# rudder_shield.net
KiCad netlist of a schematic drawn in EAGLE
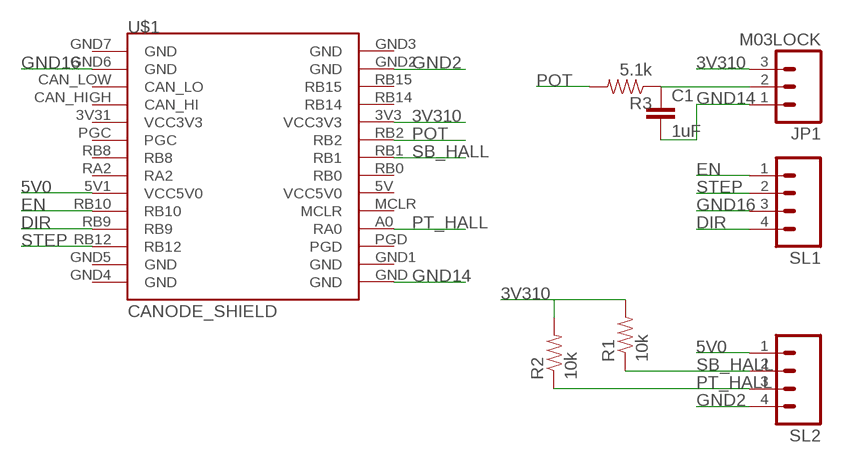
[diagram p0: schematic, sheet 1]

(export (version "E")
  (design (tool "Eeschema 10.0.6"))
  (components
    (comp (ref "C1")
      (value "1uF")
      (footprint "eagle-import:1206")
      (libsource (lib "eagle-import") (part "CAP1206"))
    )
    (comp (ref "JP1")
      (value "M03LOCK")
      (footprint "eagle-import:1X03_LOCK")
      (libsource (lib "eagle-import") (part "M03LOCK"))
    )
    (comp (ref "R1")
      (value "10k")
      (footprint "eagle-import:0805")
      (libsource (lib "eagle-import") (part "RESISTOR0805-RES"))
    )
    (comp (ref "R2")
      (value "10k")
      (footprint "eagle-import:0805")
      (libsource (lib "eagle-import") (part "RESISTOR0805-RES"))
    )
    (comp (ref "R3")
      (value "5.1k")
      (footprint "eagle-import:0805")
      (libsource (lib "eagle-import") (part "RESISTOR0805-RES"))
    )
    (comp (ref "SL1")
      (value "M04LOCK")
      (footprint "eagle-import:1X04_LOCK")
      (libsource (lib "eagle-import") (part "M04LOCK"))
    )
    (comp (ref "SL2")
      (value "M04LOCK")
      (footprint "eagle-import:1X04_LOCK")
      (libsource (lib "eagle-import") (part "M04LOCK"))
    )
    (comp (ref "U$1")
      (value "CANODE_SHIELD")
      (footprint "eagle-import:CANODE_SHIELD")
      (libsource (lib "eagle-import") (part "CANODE_SHIELD"))
    )
  )
  (nets
    (net (code "1") (name "/3V310") (class "Default")
      (node (ref "JP1") (pin "3") (pinfunction "3_3") (pintype "passive"))
      (node (ref "R1") (pin "2") (pinfunction "2_2") (pintype "passive"))
      (node (ref "R2") (pin "2") (pinfunction "2_2") (pintype "passive"))
      (node (ref "U$1") (pin "3V3") (pinfunction "VCC3V3_3V3") (pintype "bidirectional"))
    )
    (net (code "2") (name "/5V0") (class "Default")
      (node (ref "SL2") (pin "1") (pinfunction "1_1") (pintype "passive"))
      (node (ref "U$1") (pin "5V1") (pinfunction "VCC5V0_5V1") (pintype "bidirectional"))
    )
    (net (code "3") (name "/DIR") (class "Default")
      (node (ref "SL1") (pin "4") (pinfunction "4_4") (pintype "passive"))
      (node (ref "U$1") (pin "RB9") (pinfunction "RB9_RB9") (pintype "bidirectional"))
    )
    (net (code "4") (name "/EN") (class "Default")
      (node (ref "SL1") (pin "1") (pinfunction "1_1") (pintype "passive"))
      (node (ref "U$1") (pin "RB10") (pinfunction "RB10_RB10") (pintype "bidirectional"))
    )
    (net (code "5") (name "/GND2") (class "Default")
      (node (ref "SL2") (pin "4") (pinfunction "4_4") (pintype "passive"))
      (node (ref "U$1") (pin "GND2") (pinfunction "GND_GND2") (pintype "bidirectional"))
    )
    (net (code "6") (name "/GND14") (class "Default")
      (node (ref "C1") (pin "2") (pinfunction "2_2") (pintype "passive"))
      (node (ref "JP1") (pin "1") (pinfunction "1_1") (pintype "passive"))
      (node (ref "U$1") (pin "GND") (pinfunction "GND_GND") (pintype "bidirectional"))
    )
    (net (code "7") (name "/GND16") (class "Default")
      (node (ref "SL1") (pin "3") (pinfunction "3_3") (pintype "passive"))
      (node (ref "U$1") (pin "GND6") (pinfunction "GND_GND6") (pintype "bidirectional"))
    )
    (net (code "8") (name "/POT") (class "Default")
      (node (ref "R3") (pin "2") (pinfunction "2_2") (pintype "passive"))
      (node (ref "U$1") (pin "RB2") (pinfunction "RB2_RB2") (pintype "bidirectional"))
    )
    (net (code "9") (name "/PT_HALL") (class "Default")
      (node (ref "R2") (pin "1") (pinfunction "1_1") (pintype "passive"))
      (node (ref "SL2") (pin "3") (pinfunction "3_3") (pintype "passive"))
      (node (ref "U$1") (pin "A0") (pinfunction "RA0_A0") (pintype "bidirectional"))
    )
    (net (code "10") (name "/SB_HALL") (class "Default")
      (node (ref "R1") (pin "1") (pinfunction "1_1") (pintype "passive"))
      (node (ref "SL2") (pin "2") (pinfunction "2_2") (pintype "passive"))
      (node (ref "U$1") (pin "RB1") (pinfunction "RB1_RB1") (pintype "bidirectional"))
    )
    (net (code "11") (name "/STEP") (class "Default")
      (node (ref "SL1") (pin "2") (pinfunction "2_2") (pintype "passive"))
      (node (ref "U$1") (pin "RB12") (pinfunction "RB12_RB12") (pintype "bidirectional"))
    )
    (net (code "12") (name "Net-(C1-Pad1)") (class "Default")
      (node (ref "C1") (pin "1") (pinfunction "1_1") (pintype "passive"))
      (node (ref "JP1") (pin "2") (pinfunction "2_2") (pintype "passive"))
      (node (ref "R3") (pin "1") (pinfunction "1_1") (pintype "passive"))
    )
    (net (code "13") (name "unconnected-(U$1-CAN_HI-PadCAN_HIGH)") (class "Default")
      (node (ref "U$1") (pin "CAN_HIGH") (pinfunction "CAN_HI_CAN_HIGH") (pintype "bidirectional"))
    )
    (net (code "14") (name "unconnected-(U$1-CAN_LO-PadCAN_LOW)") (class "Default")
      (node (ref "U$1") (pin "CAN_LOW") (pinfunction "CAN_LO_CAN_LOW") (pintype "bidirectional"))
    )
    (net (code "15") (name "unconnected-(U$1-GND-PadGND1)") (class "Default")
      (node (ref "U$1") (pin "GND1") (pinfunction "GND_GND1") (pintype "bidirectional"))
    )
    (net (code "16") (name "unconnected-(U$1-GND-PadGND3)") (class "Default")
      (node (ref "U$1") (pin "GND3") (pinfunction "GND_GND3") (pintype "bidirectional"))
    )
    (net (code "17") (name "unconnected-(U$1-GND-PadGND4)") (class "Default")
      (node (ref "U$1") (pin "GND4") (pinfunction "GND_GND4") (pintype "bidirectional"))
    )
    (net (code "18") (name "unconnected-(U$1-GND-PadGND5)") (class "Default")
      (node (ref "U$1") (pin "GND5") (pinfunction "GND_GND5") (pintype "bidirectional"))
    )
    (net (code "19") (name "unconnected-(U$1-GND-PadGND7)") (class "Default")
      (node (ref "U$1") (pin "GND7") (pinfunction "GND_GND7") (pintype "bidirectional"))
    )
    (net (code "20") (name "unconnected-(U$1-PadMCLR)") (class "Default")
      (node (ref "U$1") (pin "MCLR") (pinfunction "MCLR_MCLR") (pintype "bidirectional"))
    )
    (net (code "21") (name "unconnected-(U$1-PadPGC)") (class "Default")
      (node (ref "U$1") (pin "PGC") (pinfunction "PGC_PGC") (pintype "bidirectional"))
    )
    (net (code "22") (name "unconnected-(U$1-PadPGD)") (class "Default")
      (node (ref "U$1") (pin "PGD") (pinfunction "PGD_PGD") (pintype "bidirectional"))
    )
    (net (code "23") (name "unconnected-(U$1-PadRA2)") (class "Default")
      (node (ref "U$1") (pin "RA2") (pinfunction "RA2_RA2") (pintype "bidirectional"))
    )
    (net (code "24") (name "unconnected-(U$1-PadRB0)") (class "Default")
      (node (ref "U$1") (pin "RB0") (pinfunction "RB0_RB0") (pintype "bidirectional"))
    )
    (net (code "25") (name "unconnected-(U$1-PadRB8)") (class "Default")
      (node (ref "U$1") (pin "RB8") (pinfunction "RB8_RB8") (pintype "bidirectional"))
    )
    (net (code "26") (name "unconnected-(U$1-PadRB14)") (class "Default")
      (node (ref "U$1") (pin "RB14") (pinfunction "RB14_RB14") (pintype "bidirectional"))
    )
    (net (code "27") (name "unconnected-(U$1-PadRB15)") (class "Default")
      (node (ref "U$1") (pin "RB15") (pinfunction "RB15_RB15") (pintype "bidirectional"))
    )
    (net (code "28") (name "unconnected-(U$1-VCC3V3-Pad3V31)") (class "Default")
      (node (ref "U$1") (pin "3V31") (pinfunction "VCC3V3_3V31") (pintype "bidirectional"))
    )
    (net (code "29") (name "unconnected-(U$1-VCC5V0-Pad5V)") (class "Default")
      (node (ref "U$1") (pin "5V") (pinfunction "VCC5V0_5V") (pintype "bidirectional"))
    )
  )
)
